# IrrigationStation_V1R1.net
KiCad netlist of a schematic drawn in Altium Designer
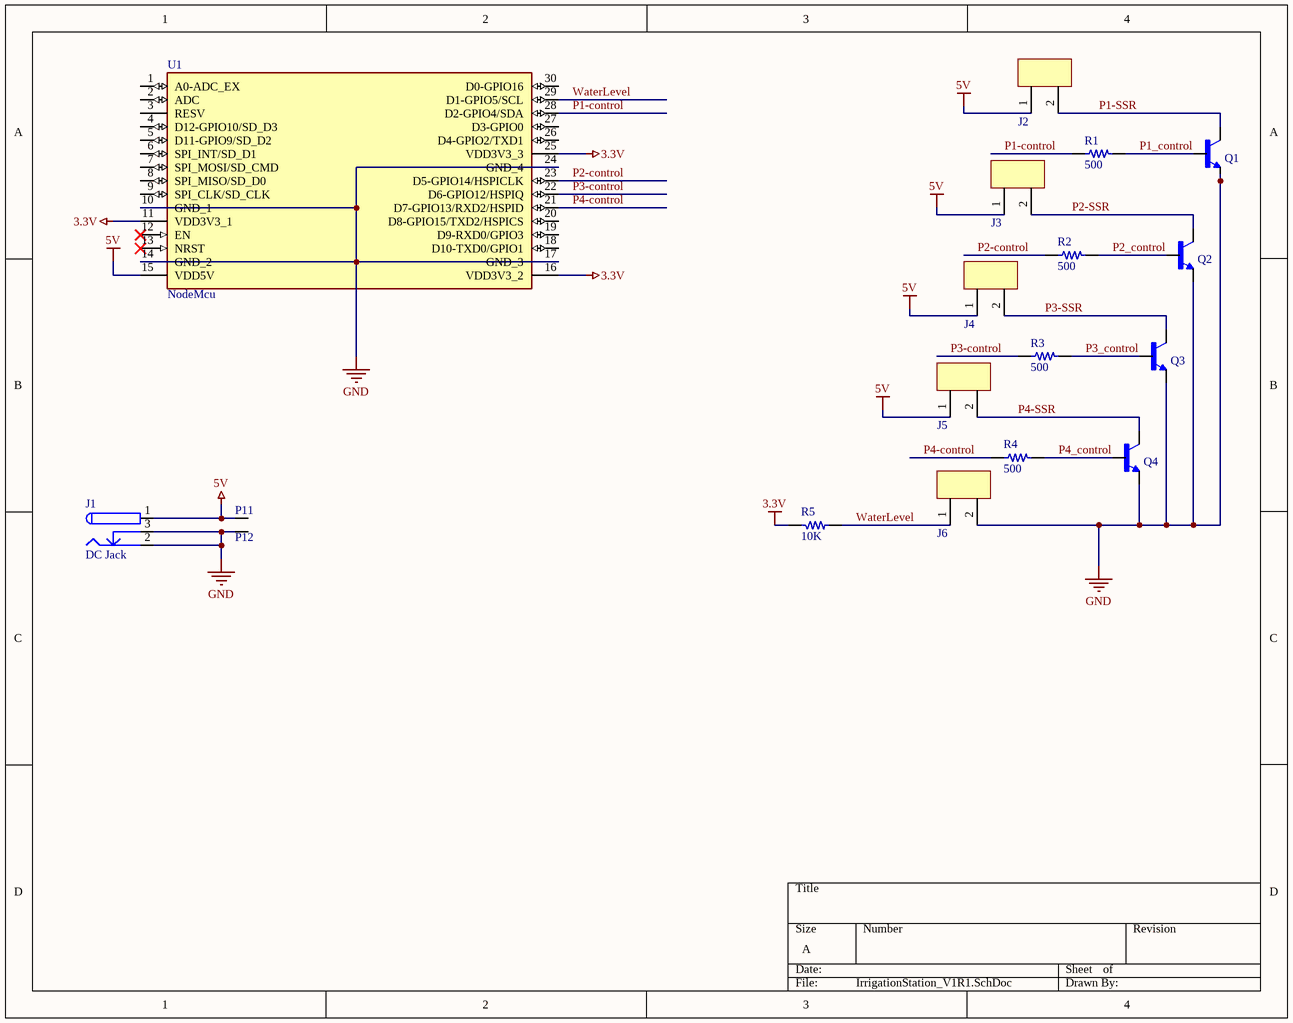
[diagram p0: IrrigationStation_V1R1.SchDoc]

(export (version "E")
  (design (tool "Eeschema 10.0.6"))
  (components
    (comp (ref "J1")
      (value "DC Jack")
      (footprint "DC Jack - KLDHCX")
      (fields
        (field (name "MANUFACTURER") "Kycon")
        (field (name "MANUFACTURER PART NUMBER") "KLDHCX-0202-AC-1")
      )
      (libsource (lib "Belle_library") (part "DC Jack"))
    )
    (comp (ref "J2")
      (value "P1")
      (footprint "Terminal Block,2 Pos, 4mm")
      (description "2 Position Terminal Block Plug, Female Sockets 180° Free Hanging (In-Line)")
      (libsource (lib "Belle_library") (part "TERM BLOCK PLUG 2POS"))
    )
    (comp (ref "J3")
      (value "P2")
      (footprint "Terminal Block,2 Pos, 4mm")
      (description "2 Position Terminal Block Plug, Female Sockets 180° Free Hanging (In-Line)")
      (libsource (lib "Belle_library") (part "TERM BLOCK PLUG 2POS"))
    )
    (comp (ref "J4")
      (value "P3")
      (footprint "Terminal Block,2 Pos, 4mm")
      (description "2 Position Terminal Block Plug, Female Sockets 180° Free Hanging (In-Line)")
      (libsource (lib "Belle_library") (part "TERM BLOCK PLUG 2POS"))
    )
    (comp (ref "J5")
      (value "P4")
      (footprint "Terminal Block,2 Pos, 4mm")
      (description "2 Position Terminal Block Plug, Female Sockets 180° Free Hanging (In-Line)")
      (libsource (lib "Belle_library") (part "TERM BLOCK PLUG 2POS"))
    )
    (comp (ref "J6")
      (value "Water Level")
      (footprint "Terminal Block,2 Pos, 4mm")
      (description "2 Position Terminal Block Plug, Female Sockets 180° Free Hanging (In-Line)")
      (libsource (lib "Belle_library") (part "TERM BLOCK PLUG 2POS"))
    )
    (comp (ref "P11")
      (value "5V")
      (footprint "Pin - TH 1.5mm")
      (description "Single Pin")
      (libsource (lib "Belle_library") (part "Pin"))
    )
    (comp (ref "P12")
      (value "GND")
      (footprint "Pin - TH 1.5mm")
      (description "Single Pin")
      (libsource (lib "Belle_library") (part "Pin"))
    )
    (comp (ref "Q1")
      (value "P2N2222A")
      (footprint "TO92")
      (description "Transitor lÆ°á»¡ng cá»±c _BJT_ NPN 40V 600mA 300 MHz 625mW qua lá»— TO-92-3")
      (fields (field (name "MF") "ON Semiconductor"))
      (libsource (lib "Belle_library") (part "P2N2222A"))
    )
    (comp (ref "Q2")
      (value "P2N2222A")
      (footprint "TO92")
      (description "Transitor lÆ°á»¡ng cá»±c _BJT_ NPN 40V 600mA 300 MHz 625mW qua lá»— TO-92-3")
      (fields (field (name "MF") "ON Semiconductor"))
      (libsource (lib "Belle_library") (part "P2N2222A"))
    )
    (comp (ref "Q3")
      (value "P2N2222A")
      (footprint "TO92")
      (description "Transitor lÆ°á»¡ng cá»±c _BJT_ NPN 40V 600mA 300 MHz 625mW qua lá»— TO-92-3")
      (fields (field (name "MF") "ON Semiconductor"))
      (libsource (lib "Belle_library") (part "P2N2222A"))
    )
    (comp (ref "Q4")
      (value "P2N2222A")
      (footprint "TO92")
      (description "Transitor lÆ°á»¡ng cá»±c _BJT_ NPN 40V 600mA 300 MHz 625mW qua lá»— TO-92-3")
      (fields (field (name "MF") "ON Semiconductor"))
      (libsource (lib "Belle_library") (part "P2N2222A"))
    )
    (comp (ref "R1")
      (value "500")
      (footprint "Resistor - TH - 12mm")
      (description "Generic Resistor")
      (libsource (lib "Belle_library") (part "Resistor"))
    )
    (comp (ref "R2")
      (value "500")
      (footprint "Resistor - TH - 12mm")
      (description "Generic Resistor")
      (libsource (lib "Belle_library") (part "Resistor"))
    )
    (comp (ref "R3")
      (value "500")
      (footprint "Resistor - TH - 12mm")
      (description "Generic Resistor")
      (libsource (lib "Belle_library") (part "Resistor"))
    )
    (comp (ref "R4")
      (value "500")
      (footprint "Resistor - TH - 12mm")
      (description "Generic Resistor")
      (libsource (lib "Belle_library") (part "Resistor"))
    )
    (comp (ref "R5")
      (value "10K")
      (footprint "Resistor - TH - 12mm")
      (description "Generic Resistor")
      (libsource (lib "Belle_library") (part "Resistor"))
    )
    (comp (ref "U1")
      (value "NodeMcu")
      (footprint "DIP2286W64P254L4826H735Q30N")
      (description "Undefined or Miscellaneous")
      (fields
        (field (name "MANUFACTURER_PART_NUMBER") "113990105")
        (field (name "MOUSER PART NUMBER") "713-113990105")
      )
      (libsource (lib "Belle_library") (part "NodeMcu"))
    )
  )
  (nets
    (net (code "1") (name "/P1-SSR") (class "Default")
      (node (ref "J2") (pin "2") (pintype "passive"))
      (node (ref "Q1") (pin "3") (pinfunction "C_3") (pintype "passive"))
    )
    (net (code "2") (name "/P1-control") (class "Default")
      (node (ref "R1") (pin "1") (pinfunction "1_1") (pintype "passive"))
      (node (ref "U1") (pin "28") (pinfunction "D2-GPIO4/SDA_28") (pintype "bidirectional"))
    )
    (net (code "3") (name "/P1_control") (class "Default")
      (node (ref "Q1") (pin "2") (pinfunction "B_2") (pintype "passive"))
      (node (ref "R1") (pin "2") (pinfunction "2_2") (pintype "passive"))
    )
    (net (code "4") (name "/P2-SSR") (class "Default")
      (node (ref "J3") (pin "2") (pintype "passive"))
      (node (ref "Q2") (pin "3") (pinfunction "C_3") (pintype "passive"))
    )
    (net (code "5") (name "/P2-control") (class "Default")
      (node (ref "R2") (pin "1") (pinfunction "1_1") (pintype "passive"))
      (node (ref "U1") (pin "23") (pinfunction "D5-GPIO14/HSPICLK_23") (pintype "bidirectional"))
    )
    (net (code "6") (name "/P2_control") (class "Default")
      (node (ref "Q2") (pin "2") (pinfunction "B_2") (pintype "passive"))
      (node (ref "R2") (pin "2") (pinfunction "2_2") (pintype "passive"))
    )
    (net (code "7") (name "/P3-SSR") (class "Default")
      (node (ref "J4") (pin "2") (pintype "passive"))
      (node (ref "Q3") (pin "3") (pinfunction "C_3") (pintype "passive"))
    )
    (net (code "8") (name "/P3-control") (class "Default")
      (node (ref "R3") (pin "1") (pinfunction "1_1") (pintype "passive"))
      (node (ref "U1") (pin "22") (pinfunction "D6-GPIO12/HSPIQ_22") (pintype "bidirectional"))
    )
    (net (code "9") (name "/P3_control") (class "Default")
      (node (ref "Q3") (pin "2") (pinfunction "B_2") (pintype "passive"))
      (node (ref "R3") (pin "2") (pinfunction "2_2") (pintype "passive"))
    )
    (net (code "10") (name "/P4-SSR") (class "Default")
      (node (ref "J5") (pin "2") (pintype "passive"))
      (node (ref "Q4") (pin "3") (pinfunction "C_3") (pintype "passive"))
    )
    (net (code "11") (name "/P4-control") (class "Default")
      (node (ref "R4") (pin "1") (pinfunction "1_1") (pintype "passive"))
      (node (ref "U1") (pin "21") (pinfunction "D7-GPIO13/RXD2/HSPID_21") (pintype "bidirectional"))
    )
    (net (code "12") (name "/P4_control") (class "Default")
      (node (ref "Q4") (pin "2") (pinfunction "B_2") (pintype "passive"))
      (node (ref "R4") (pin "2") (pinfunction "2_2") (pintype "passive"))
    )
    (net (code "13") (name "/WaterLevel") (class "Default")
      (node (ref "J6") (pin "1") (pintype "passive"))
      (node (ref "R5") (pin "1") (pinfunction "1_1") (pintype "passive"))
      (node (ref "U1") (pin "29") (pinfunction "D1-GPIO5/SCL_29") (pintype "bidirectional"))
    )
    (net (code "14") (name "3.3V") (class "Default")
      (node (ref "R5") (pin "2") (pinfunction "2_2") (pintype "passive"))
      (node (ref "U1") (pin "11") (pinfunction "VDD3V3_1_11") (pintype "power_in"))
      (node (ref "U1") (pin "16") (pinfunction "VDD3V3_2_16") (pintype "power_in"))
      (node (ref "U1") (pin "25") (pinfunction "VDD3V3_3_25") (pintype "power_in"))
    )
    (net (code "15") (name "5V") (class "Default")
      (node (ref "J1") (pin "1") (pinfunction "1_1") (pintype "power_in"))
      (node (ref "J2") (pin "1") (pintype "passive"))
      (node (ref "J3") (pin "1") (pintype "passive"))
      (node (ref "J4") (pin "1") (pintype "passive"))
      (node (ref "J5") (pin "1") (pintype "passive"))
      (node (ref "P11") (pin "1") (pinfunction "1_1") (pintype "passive"))
      (node (ref "U1") (pin "15") (pinfunction "VDD5V_15") (pintype "power_in"))
    )
    (net (code "16") (name "GND") (class "Default")
      (node (ref "J1") (pin "2") (pinfunction "2_2") (pintype "power_in"))
      (node (ref "J1") (pin "3") (pinfunction "3_3") (pintype "power_in"))
      (node (ref "J6") (pin "2") (pintype "passive"))
      (node (ref "P12") (pin "1") (pinfunction "1_1") (pintype "passive"))
      (node (ref "Q1") (pin "1") (pinfunction "E_1") (pintype "passive"))
      (node (ref "Q2") (pin "1") (pinfunction "E_1") (pintype "passive"))
      (node (ref "Q3") (pin "1") (pinfunction "E_1") (pintype "passive"))
      (node (ref "Q4") (pin "1") (pinfunction "E_1") (pintype "passive"))
      (node (ref "U1") (pin "10") (pinfunction "GND_1_10") (pintype "power_in"))
      (node (ref "U1") (pin "14") (pinfunction "GND_2_14") (pintype "power_in"))
      (node (ref "U1") (pin "17") (pinfunction "GND_3_17") (pintype "power_in"))
      (node (ref "U1") (pin "24") (pinfunction "GND_4_24") (pintype "power_in"))
    )
    (net (code "17") (name "unconnected-(U1-A0-ADC_EX-Pad1)") (class "Default")
      (node (ref "U1") (pin "1") (pinfunction "A0-ADC_EX_1") (pintype "bidirectional"))
    )
    (net (code "18") (name "unconnected-(U1-ADC-Pad2)") (class "Default")
      (node (ref "U1") (pin "2") (pinfunction "ADC_2") (pintype "bidirectional"))
    )
    (net (code "19") (name "unconnected-(U1-D0-GPIO16-Pad30)") (class "Default")
      (node (ref "U1") (pin "30") (pinfunction "D0-GPIO16_30") (pintype "bidirectional"))
    )
    (net (code "20") (name "unconnected-(U1-D3-GPIO0-Pad27)") (class "Default")
      (node (ref "U1") (pin "27") (pinfunction "D3-GPIO0_27") (pintype "bidirectional"))
    )
    (net (code "21") (name "unconnected-(U1-D4-GPIO2{slash}TXD1-Pad26)") (class "Default")
      (node (ref "U1") (pin "26") (pinfunction "D4-GPIO2/TXD1_26") (pintype "bidirectional"))
    )
    (net (code "22") (name "unconnected-(U1-D8-GPIO15{slash}TXD2{slash}HSPICS-Pad20)") (class "Default")
      (node (ref "U1") (pin "20") (pinfunction "D8-GPIO15/TXD2/HSPICS_20") (pintype "bidirectional"))
    )
    (net (code "23") (name "unconnected-(U1-D9-RXD0{slash}GPIO3-Pad19)") (class "Default")
      (node (ref "U1") (pin "19") (pinfunction "D9-RXD0/GPIO3_19") (pintype "bidirectional"))
    )
    (net (code "24") (name "unconnected-(U1-D10-TXD0{slash}GPIO1-Pad18)") (class "Default")
      (node (ref "U1") (pin "18") (pinfunction "D10-TXD0/GPIO1_18") (pintype "bidirectional"))
    )
    (net (code "25") (name "unconnected-(U1-D11-GPIO9{slash}SD_D2-Pad5)") (class "Default")
      (node (ref "U1") (pin "5") (pinfunction "D11-GPIO9/SD_D2_5") (pintype "bidirectional"))
    )
    (net (code "26") (name "unconnected-(U1-D12-GPIO10{slash}SD_D3-Pad4)") (class "Default")
      (node (ref "U1") (pin "4") (pinfunction "D12-GPIO10/SD_D3_4") (pintype "bidirectional"))
    )
    (net (code "27") (name "unconnected-(U1-EN-Pad12)") (class "Default")
      (node (ref "U1") (pin "12") (pinfunction "EN_12") (pintype "input+no_connect"))
    )
    (net (code "28") (name "unconnected-(U1-NRST-Pad13)") (class "Default")
      (node (ref "U1") (pin "13") (pinfunction "NRST_13") (pintype "input+no_connect"))
    )
    (net (code "29") (name "unconnected-(U1-RESV-Pad3)") (class "Default")
      (node (ref "U1") (pin "3") (pinfunction "RESV_3") (pintype "passive"))
    )
    (net (code "30") (name "unconnected-(U1-SPI_CLK{slash}SD_CLK-Pad9)") (class "Default")
      (node (ref "U1") (pin "9") (pinfunction "SPI_CLK/SD_CLK_9") (pintype "bidirectional"))
    )
    (net (code "31") (name "unconnected-(U1-SPI_INT{slash}SD_D1-Pad6)") (class "Default")
      (node (ref "U1") (pin "6") (pinfunction "SPI_INT/SD_D1_6") (pintype "bidirectional"))
    )
    (net (code "32") (name "unconnected-(U1-SPI_MISO{slash}SD_D0-Pad8)") (class "Default")
      (node (ref "U1") (pin "8") (pinfunction "SPI_MISO/SD_D0_8") (pintype "bidirectional"))
    )
    (net (code "33") (name "unconnected-(U1-SPI_MOSI{slash}SD_CMD-Pad7)") (class "Default")
      (node (ref "U1") (pin "7") (pinfunction "SPI_MOSI/SD_CMD_7") (pintype "bidirectional"))
    )
  )
)
